# timer.net
KiCad netlist of a schematic drawn in EAGLE
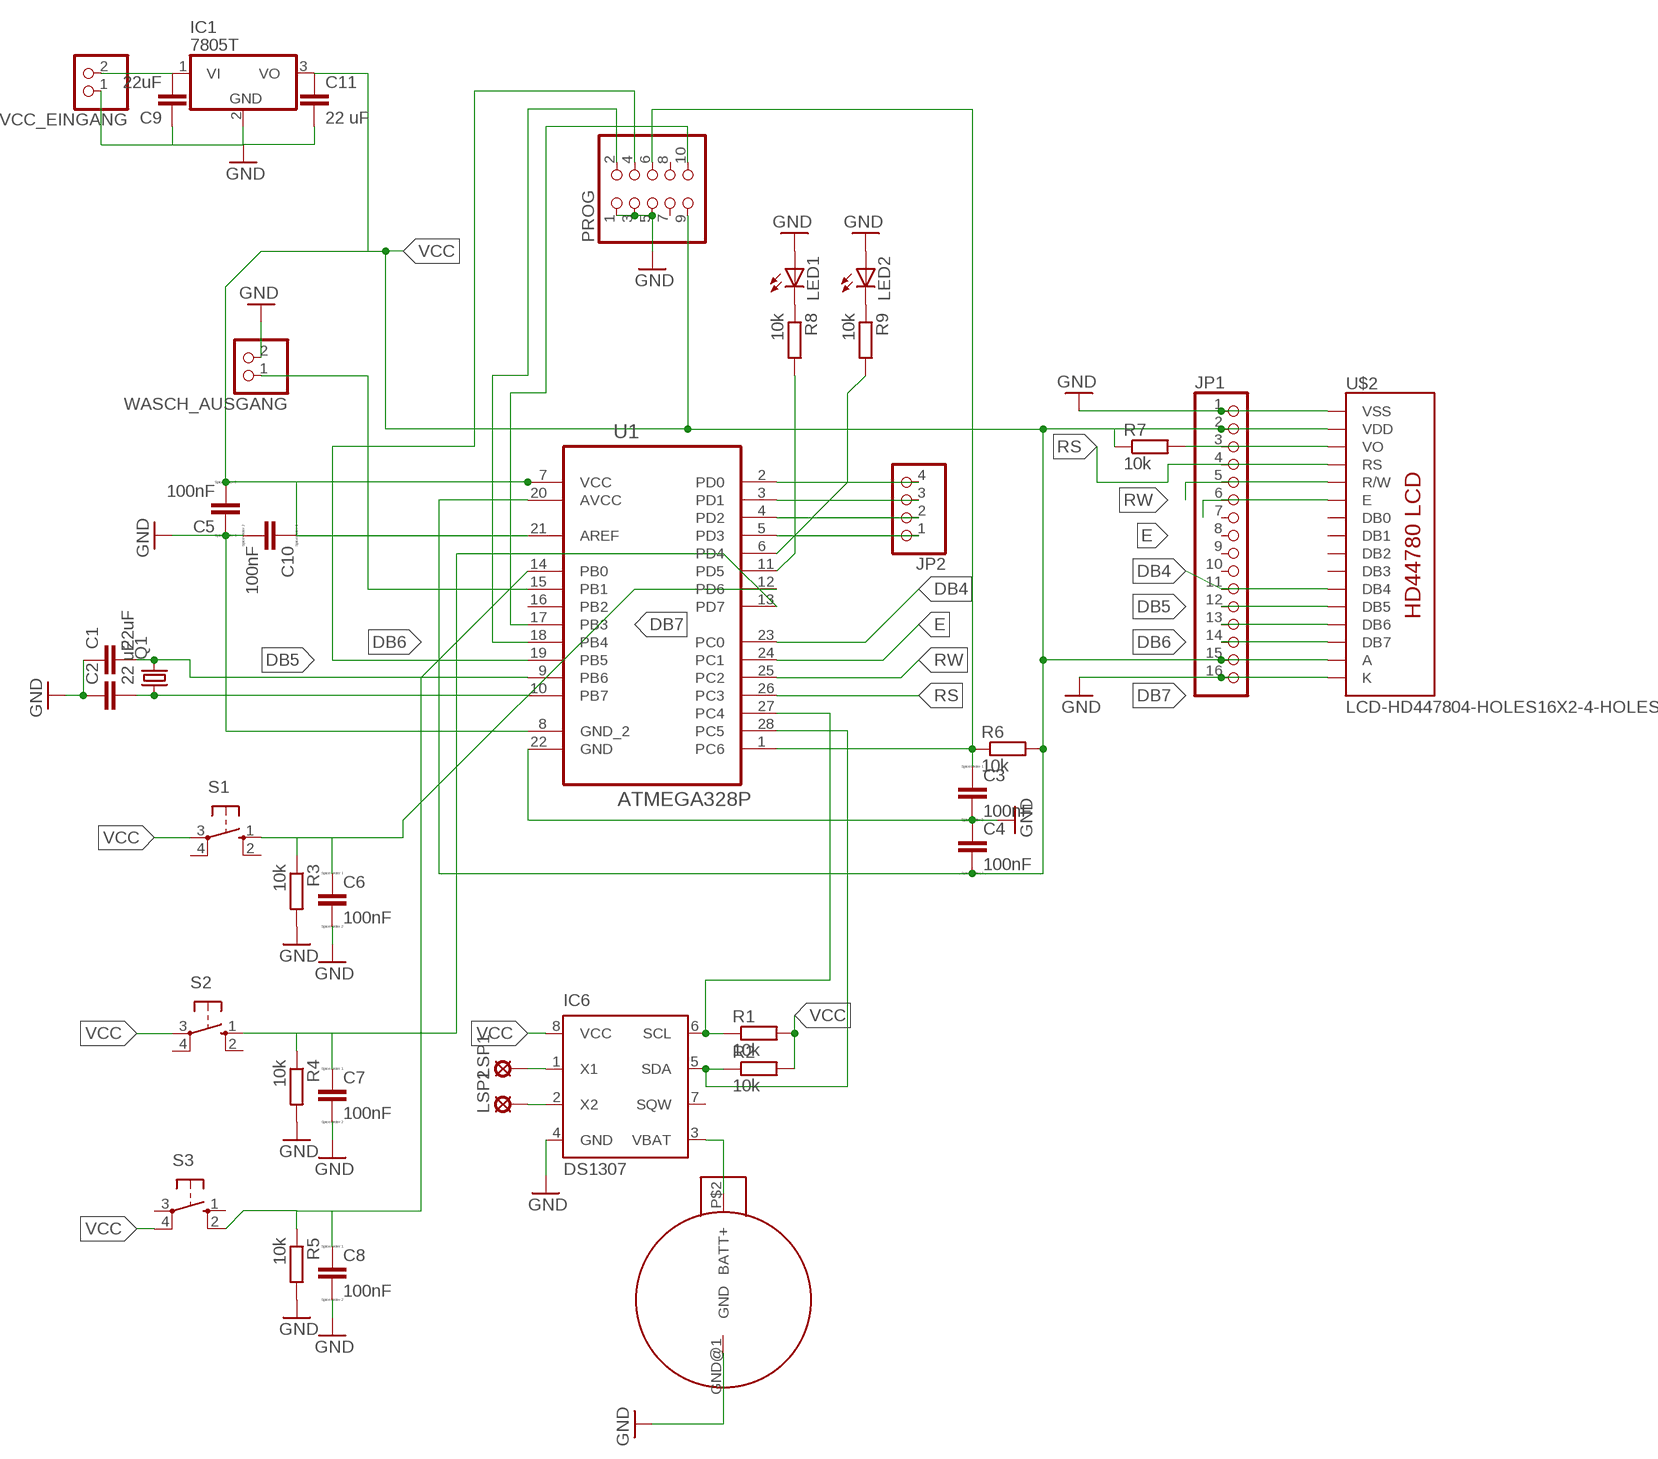
[diagram p0: schematic, sheet 1]

(export (version "E")
  (design (tool "Eeschema 10.0.6"))
  (components
    (comp (ref "C1")
      (value "22uF")
      (footprint "eagle-import:C025-025X050")
      (libsource (lib "eagle-import") (part "C-EU025-025X050"))
    )
    (comp (ref "C2")
      (value "22 uF")
      (footprint "eagle-import:C025-025X050")
      (libsource (lib "eagle-import") (part "C-EU025-025X050"))
    )
    (comp (ref "C3")
      (value "100nF")
      (footprint "eagle-import:C0603")
      (libsource (lib "eagle-import") (part "CC0603"))
    )
    (comp (ref "C4")
      (value "100nF")
      (footprint "eagle-import:C0603")
      (libsource (lib "eagle-import") (part "CC0603"))
    )
    (comp (ref "C5")
      (value "100nF")
      (footprint "eagle-import:C0603")
      (libsource (lib "eagle-import") (part "CC0603"))
    )
    (comp (ref "C6")
      (value "100nF")
      (footprint "eagle-import:C0603")
      (libsource (lib "eagle-import") (part "CC0603"))
    )
    (comp (ref "C7")
      (value "100nF")
      (footprint "eagle-import:C0603")
      (libsource (lib "eagle-import") (part "CC0603"))
    )
    (comp (ref "C8")
      (value "100nF")
      (footprint "eagle-import:C0603")
      (libsource (lib "eagle-import") (part "CC0603"))
    )
    (comp (ref "C9")
      (value "22uF")
      (footprint "eagle-import:C025-025X050")
      (libsource (lib "eagle-import") (part "C-EU025-025X050"))
    )
    (comp (ref "C10")
      (value "100nF")
      (footprint "eagle-import:C0603")
      (libsource (lib "eagle-import") (part "CC0603"))
    )
    (comp (ref "C11")
      (value "22 uF")
      (footprint "eagle-import:C025-025X050")
      (libsource (lib "eagle-import") (part "C-EU025-025X050"))
    )
    (comp (ref "IC1")
      (value "7805T")
      (footprint "eagle-import:TO220H")
      (libsource (lib "eagle-import") (part "78T05"))
    )
    (comp (ref "IC6")
      (value "DS1307")
      (footprint "eagle-import:DIL08")
      (libsource (lib "eagle-import") (part "DS1307"))
    )
    (comp (ref "JP1")
      (value "PINHD-1X16")
      (footprint "eagle-import:1X16")
      (libsource (lib "eagle-import") (part "PINHD-1X16"))
    )
    (comp (ref "JP2")
      (value "PINHD-1X4/90")
      (footprint "eagle-import:1X04_90")
      (libsource (lib "eagle-import") (part "PINHD-1X4/90"))
    )
    (comp (ref "LED1")
      (value "LED5MM")
      (footprint "eagle-import:LED5MM")
      (libsource (lib "eagle-import") (part "LED5MM"))
    )
    (comp (ref "LED2")
      (value "LED5MM")
      (footprint "eagle-import:LED5MM")
      (libsource (lib "eagle-import") (part "LED5MM"))
    )
    (comp (ref "LSP1")
      (value "LSP10")
      (footprint "eagle-import:LSP10")
      (libsource (lib "eagle-import") (part "LSP10"))
    )
    (comp (ref "LSP2")
      (value "LSP10")
      (footprint "eagle-import:LSP10")
      (libsource (lib "eagle-import") (part "LSP10"))
    )
    (comp (ref "PROG")
      (value "PINHD-2X5")
      (footprint "eagle-import:2X05")
      (libsource (lib "eagle-import") (part "PINHD-2X5"))
    )
    (comp (ref "Q1")
      (value "CRYSTALHC49U-V")
      (footprint "eagle-import:HC49U-V")
      (libsource (lib "eagle-import") (part "CRYSTALHC49U-V"))
    )
    (comp (ref "R1")
      (value "10k")
      (footprint "eagle-import:0204_7")
      (libsource (lib "eagle-import") (part "R-EU_0204/7"))
    )
    (comp (ref "R2")
      (value "10k")
      (footprint "eagle-import:0204_7")
      (libsource (lib "eagle-import") (part "R-EU_0204/7"))
    )
    (comp (ref "R3")
      (value "10k")
      (footprint "eagle-import:0204_7")
      (libsource (lib "eagle-import") (part "R-EU_0204/7"))
    )
    (comp (ref "R4")
      (value "10k")
      (footprint "eagle-import:0204_7")
      (libsource (lib "eagle-import") (part "R-EU_0204/7"))
    )
    (comp (ref "R5")
      (value "10k")
      (footprint "eagle-import:0204_7")
      (libsource (lib "eagle-import") (part "R-EU_0204/7"))
    )
    (comp (ref "R6")
      (value "10k")
      (footprint "eagle-import:0204_7")
      (libsource (lib "eagle-import") (part "R-EU_0204/7"))
    )
    (comp (ref "R7")
      (value "10k")
      (footprint "eagle-import:0204_7")
      (libsource (lib "eagle-import") (part "R-EU_0204/7"))
    )
    (comp (ref "R8")
      (value "10k")
      (footprint "eagle-import:0204_7")
      (libsource (lib "eagle-import") (part "R-EU_0204/7"))
    )
    (comp (ref "R9")
      (value "10k")
      (footprint "eagle-import:0204_7")
      (libsource (lib "eagle-import") (part "R-EU_0204/7"))
    )
    (comp (ref "S1")
      (value "10-XX")
      (footprint "eagle-import:B3F-10XX")
      (fields (field (name "MPN") "B3F-1000"))
      (libsource (lib "eagle-import") (part "10-XX"))
    )
    (comp (ref "S2")
      (value "10-XX")
      (footprint "eagle-import:B3F-10XX")
      (fields (field (name "MPN") "B3F-1000"))
      (libsource (lib "eagle-import") (part "10-XX"))
    )
    (comp (ref "S3")
      (value "10-XX")
      (footprint "eagle-import:B3F-10XX")
      (fields (field (name "MPN") "B3F-1000"))
      (libsource (lib "eagle-import") (part "10-XX"))
    )
    (comp (ref "U$1")
      (value "CR2032")
      (footprint "eagle-import:CR2023")
      (libsource (lib "eagle-import") (part "CR2032"))
    )
    (comp (ref "U$2")
      (value "LCD-HD447804-HOLES16X2-4-HOLES")
      (footprint "eagle-import:LCD-16X2-4HOLES")
      (libsource (lib "eagle-import") (part "LCD-HD4478016X2-4-HOLES4-HOLES"))
    )
    (comp (ref "U1")
      (value "ATMEGA328P")
      (footprint "eagle-import:DIP254P762X457-28")
      (fields (field (name "MPN") "ATMEGA328P-PU"))
      (libsource (lib "eagle-import") (part "ATMEGA328P-PU"))
    )
    (comp (ref "VCC_EINGANG")
      (value "PINHD-1X2")
      (footprint "eagle-import:1X02")
      (libsource (lib "eagle-import") (part "PINHD-1X2"))
    )
    (comp (ref "WASCH_AUSGANG")
      (value "PINHD-1X2")
      (footprint "eagle-import:1X02")
      (libsource (lib "eagle-import") (part "PINHD-1X2"))
    )
  )
  (nets
    (net (code "1") (name "DB4") (class "Default")
      (node (ref "JP1") (pin "11") (pinfunction "11_11") (pintype "passive"))
      (node (ref "U$2") (pin "11") (pinfunction "DB4_11") (pintype "bidirectional"))
      (node (ref "U1") (pin "23") (pinfunction "PC0_23") (pintype "bidirectional"))
    )
    (net (code "2") (name "DB5") (class "Default")
      (node (ref "JP1") (pin "12") (pinfunction "12_12") (pintype "passive"))
      (node (ref "PROG") (pin "4") (pinfunction "4_4") (pintype "passive"))
      (node (ref "U$2") (pin "12") (pinfunction "DB5_12") (pintype "bidirectional"))
      (node (ref "U1") (pin "19") (pinfunction "PB5_19") (pintype "bidirectional"))
    )
    (net (code "3") (name "DB6") (class "Default")
      (node (ref "JP1") (pin "13") (pinfunction "13_13") (pintype "passive"))
      (node (ref "PROG") (pin "2") (pinfunction "2_2") (pintype "passive"))
      (node (ref "U$2") (pin "13") (pinfunction "DB6_13") (pintype "bidirectional"))
      (node (ref "U1") (pin "18") (pinfunction "PB4_18") (pintype "bidirectional"))
    )
    (net (code "4") (name "DB7") (class "Default")
      (node (ref "JP1") (pin "14") (pinfunction "14_14") (pintype "passive"))
      (node (ref "PROG") (pin "10") (pinfunction "10_10") (pintype "passive"))
      (node (ref "U$2") (pin "14") (pinfunction "DB7_14") (pintype "bidirectional"))
      (node (ref "U1") (pin "17") (pinfunction "PB3_17") (pintype "bidirectional"))
    )
    (net (code "5") (name "E") (class "Default")
      (node (ref "JP1") (pin "6") (pinfunction "6_6") (pintype "passive"))
      (node (ref "U$2") (pin "6") (pinfunction "E_6") (pintype "input"))
      (node (ref "U1") (pin "24") (pinfunction "PC1_24") (pintype "bidirectional"))
    )
    (net (code "6") (name "GND") (class "Default")
      (node (ref "C1") (pin "1") (pinfunction "1_1") (pintype "passive"))
      (node (ref "C10") (pin "2") (pinfunction "2_2") (pintype "passive"))
      (node (ref "C11") (pin "2") (pinfunction "2_2") (pintype "passive"))
      (node (ref "C2") (pin "1") (pinfunction "1_1") (pintype "passive"))
      (node (ref "C3") (pin "2") (pinfunction "2_2") (pintype "passive"))
      (node (ref "C4") (pin "1") (pinfunction "1_1") (pintype "passive"))
      (node (ref "C5") (pin "1") (pinfunction "1_1") (pintype "passive"))
      (node (ref "C6") (pin "2") (pinfunction "2_2") (pintype "passive"))
      (node (ref "C7") (pin "2") (pinfunction "2_2") (pintype "passive"))
      (node (ref "C8") (pin "2") (pinfunction "2_2") (pintype "passive"))
      (node (ref "C9") (pin "1") (pinfunction "1_1") (pintype "passive"))
      (node (ref "IC1") (pin "2") (pinfunction "GND_2") (pintype "passive"))
      (node (ref "IC6") (pin "4") (pinfunction "GND_4") (pintype "power_in"))
      (node (ref "JP1") (pin "1") (pinfunction "1_1") (pintype "passive"))
      (node (ref "JP1") (pin "16") (pinfunction "16_16") (pintype "passive"))
      (node (ref "LED1") (pin "A") (pinfunction "A_A") (pintype "passive"))
      (node (ref "LED2") (pin "A") (pinfunction "A_A") (pintype "passive"))
      (node (ref "PROG") (pin "1") (pinfunction "1_1") (pintype "passive"))
      (node (ref "PROG") (pin "3") (pinfunction "3_3") (pintype "passive"))
      (node (ref "PROG") (pin "5") (pinfunction "5_5") (pintype "passive"))
      (node (ref "R3") (pin "2") (pinfunction "2_2") (pintype "passive"))
      (node (ref "R4") (pin "2") (pinfunction "2_2") (pintype "passive"))
      (node (ref "R5") (pin "2") (pinfunction "2_2") (pintype "passive"))
      (node (ref "U$1") (pin "GND@1") (pinfunction "GND_GND@1") (pintype "power_in"))
      (node (ref "U$2") (pin "1") (pinfunction "VSS_1") (pintype "power_in"))
      (node (ref "U$2") (pin "16") (pinfunction "K_16") (pintype "power_in"))
      (node (ref "U1") (pin "22") (pinfunction "GND_22") (pintype "passive"))
      (node (ref "U1") (pin "8") (pinfunction "GND_2_8") (pintype "passive"))
      (node (ref "VCC_EINGANG") (pin "1") (pinfunction "1_1") (pintype "passive"))
      (node (ref "WASCH_AUSGANG") (pin "2") (pinfunction "2_2") (pintype "passive"))
    )
    (net (code "7") (name "Net-(IC1-VI)") (class "Default")
      (node (ref "C9") (pin "2") (pinfunction "2_2") (pintype "passive"))
      (node (ref "IC1") (pin "1") (pinfunction "VI_1") (pintype "input"))
      (node (ref "VCC_EINGANG") (pin "2") (pinfunction "2_2") (pintype "passive"))
    )
    (net (code "8") (name "Net-(IC6-SCL)") (class "Default")
      (node (ref "IC6") (pin "6") (pinfunction "SCL_6") (pintype "input"))
      (node (ref "R1") (pin "1") (pinfunction "1_1") (pintype "passive"))
      (node (ref "U1") (pin "27") (pinfunction "PC4_27") (pintype "bidirectional"))
    )
    (net (code "9") (name "Net-(IC6-SDA)") (class "Default")
      (node (ref "IC6") (pin "5") (pinfunction "SDA_5") (pintype "bidirectional"))
      (node (ref "R2") (pin "1") (pinfunction "1_1") (pintype "passive"))
      (node (ref "U1") (pin "28") (pinfunction "PC5_28") (pintype "bidirectional"))
    )
    (net (code "10") (name "Net-(IC6-VBAT)") (class "Default")
      (node (ref "IC6") (pin "3") (pinfunction "VBAT_3") (pintype "passive"))
      (node (ref "U$1") (pin "P$2") (pinfunction "BATT+_P$2") (pintype "output"))
    )
    (net (code "11") (name "Net-(IC6-X1)") (class "Default")
      (node (ref "IC6") (pin "1") (pinfunction "X1_1") (pintype "input"))
      (node (ref "LSP1") (pin "MP") (pinfunction "MP_MP") (pintype "passive"))
    )
    (net (code "12") (name "Net-(IC6-X2)") (class "Default")
      (node (ref "IC6") (pin "2") (pinfunction "X2_2") (pintype "output"))
      (node (ref "LSP2") (pin "MP") (pinfunction "MP_MP") (pintype "passive"))
    )
    (net (code "13") (name "Net-(LED1-C)") (class "Default")
      (node (ref "LED1") (pin "K") (pinfunction "C_K") (pintype "passive"))
      (node (ref "R8") (pin "1") (pinfunction "1_1") (pintype "passive"))
    )
    (net (code "14") (name "Net-(LED2-C)") (class "Default")
      (node (ref "LED2") (pin "K") (pinfunction "C_K") (pintype "passive"))
      (node (ref "R9") (pin "1") (pinfunction "1_1") (pintype "passive"))
    )
    (net (code "15") (name "Net-(S1-S)") (class "Default")
      (node (ref "C6") (pin "1") (pinfunction "1_1") (pintype "passive"))
      (node (ref "R3") (pin "1") (pinfunction "1_1") (pintype "passive"))
      (node (ref "S1") (pin "1") (pinfunction "S_1") (pintype "passive"))
      (node (ref "U1") (pin "12") (pinfunction "PD6_12") (pintype "bidirectional"))
    )
    (net (code "16") (name "Net-(S2-S)") (class "Default")
      (node (ref "C7") (pin "1") (pinfunction "1_1") (pintype "passive"))
      (node (ref "R4") (pin "1") (pinfunction "1_1") (pintype "passive"))
      (node (ref "S2") (pin "1") (pinfunction "S_1") (pintype "passive"))
      (node (ref "U1") (pin "13") (pinfunction "PD7_13") (pintype "bidirectional"))
    )
    (net (code "17") (name "Net-(S3-S1)") (class "Default")
      (node (ref "C8") (pin "1") (pinfunction "1_1") (pintype "passive"))
      (node (ref "R5") (pin "1") (pinfunction "1_1") (pintype "passive"))
      (node (ref "S3") (pin "2") (pinfunction "S1_2") (pintype "passive"))
      (node (ref "U1") (pin "14") (pinfunction "PB0_14") (pintype "bidirectional"))
    )
    (net (code "18") (name "Net-(U$2-VO)") (class "Default")
      (node (ref "JP1") (pin "3") (pinfunction "3_3") (pintype "passive"))
      (node (ref "R7") (pin "2") (pinfunction "2_2") (pintype "passive"))
      (node (ref "U$2") (pin "3") (pinfunction "VO_3") (pintype "bidirectional"))
    )
    (net (code "19") (name "Net-(U1-PB1)") (class "Default")
      (node (ref "U1") (pin "15") (pinfunction "PB1_15") (pintype "bidirectional"))
      (node (ref "WASCH_AUSGANG") (pin "1") (pinfunction "1_1") (pintype "passive"))
    )
    (net (code "20") (name "Net-(U1-PB6)") (class "Default")
      (node (ref "C1") (pin "2") (pinfunction "2_2") (pintype "passive"))
      (node (ref "Q1") (pin "2") (pinfunction "2_2") (pintype "passive"))
      (node (ref "U1") (pin "9") (pinfunction "PB6_9") (pintype "bidirectional"))
    )
    (net (code "21") (name "Net-(U1-PB7)") (class "Default")
      (node (ref "C2") (pin "2") (pinfunction "2_2") (pintype "passive"))
      (node (ref "Q1") (pin "1") (pinfunction "1_1") (pintype "passive"))
      (node (ref "U1") (pin "10") (pinfunction "PB7_10") (pintype "bidirectional"))
    )
    (net (code "22") (name "Net-(U1-PC6)") (class "Default")
      (node (ref "C3") (pin "1") (pinfunction "1_1") (pintype "passive"))
      (node (ref "PROG") (pin "6") (pinfunction "6_6") (pintype "passive"))
      (node (ref "R6") (pin "1") (pinfunction "1_1") (pintype "passive"))
      (node (ref "U1") (pin "1") (pinfunction "PC6_1") (pintype "bidirectional"))
    )
    (net (code "23") (name "Net-(U1-PD0)") (class "Default")
      (node (ref "JP2") (pin "4") (pinfunction "4_4") (pintype "passive"))
      (node (ref "U1") (pin "2") (pinfunction "PD0_2") (pintype "bidirectional"))
    )
    (net (code "24") (name "Net-(U1-PD1)") (class "Default")
      (node (ref "JP2") (pin "3") (pinfunction "3_3") (pintype "passive"))
      (node (ref "U1") (pin "3") (pinfunction "PD1_3") (pintype "bidirectional"))
    )
    (net (code "25") (name "Net-(U1-PD2)") (class "Default")
      (node (ref "JP2") (pin "2") (pinfunction "2_2") (pintype "passive"))
      (node (ref "U1") (pin "4") (pinfunction "PD2_4") (pintype "bidirectional"))
    )
    (net (code "26") (name "Net-(U1-PD3)") (class "Default")
      (node (ref "JP2") (pin "1") (pinfunction "1_1") (pintype "passive"))
      (node (ref "U1") (pin "5") (pinfunction "PD3_5") (pintype "bidirectional"))
    )
    (net (code "27") (name "Net-(U1-PD4)") (class "Default")
      (node (ref "R9") (pin "2") (pinfunction "2_2") (pintype "passive"))
      (node (ref "U1") (pin "6") (pinfunction "PD4_6") (pintype "bidirectional"))
    )
    (net (code "28") (name "Net-(U1-PD5)") (class "Default")
      (node (ref "R8") (pin "2") (pinfunction "2_2") (pintype "passive"))
      (node (ref "U1") (pin "11") (pinfunction "PD5_11") (pintype "bidirectional"))
    )
    (net (code "29") (name "RS") (class "Default")
      (node (ref "JP1") (pin "4") (pinfunction "4_4") (pintype "passive"))
      (node (ref "U$2") (pin "4") (pinfunction "RS_4") (pintype "input"))
      (node (ref "U1") (pin "26") (pinfunction "PC3_26") (pintype "bidirectional"))
    )
    (net (code "30") (name "RW") (class "Default")
      (node (ref "JP1") (pin "5") (pinfunction "5_5") (pintype "passive"))
      (node (ref "U$2") (pin "5") (pinfunction "R/W_5") (pintype "input"))
      (node (ref "U1") (pin "25") (pinfunction "PC2_25") (pintype "bidirectional"))
    )
    (net (code "31") (name "VCC") (class "Default")
      (node (ref "C10") (pin "1") (pinfunction "1_1") (pintype "passive"))
      (node (ref "C11") (pin "1") (pinfunction "1_1") (pintype "passive"))
      (node (ref "C4") (pin "2") (pinfunction "2_2") (pintype "passive"))
      (node (ref "C5") (pin "2") (pinfunction "2_2") (pintype "passive"))
      (node (ref "IC1") (pin "3") (pinfunction "VO_3") (pintype "passive"))
      (node (ref "IC6") (pin "8") (pinfunction "VCC_8") (pintype "power_in"))
      (node (ref "JP1") (pin "15") (pinfunction "15_15") (pintype "passive"))
      (node (ref "JP1") (pin "2") (pinfunction "2_2") (pintype "passive"))
      (node (ref "PROG") (pin "9") (pinfunction "9_9") (pintype "passive"))
      (node (ref "R1") (pin "2") (pinfunction "2_2") (pintype "passive"))
      (node (ref "R2") (pin "2") (pinfunction "2_2") (pintype "passive"))
      (node (ref "R6") (pin "2") (pinfunction "2_2") (pintype "passive"))
      (node (ref "R7") (pin "1") (pinfunction "1_1") (pintype "passive"))
      (node (ref "S1") (pin "3") (pinfunction "P_3") (pintype "passive"))
      (node (ref "S2") (pin "3") (pinfunction "P_3") (pintype "passive"))
      (node (ref "S3") (pin "4") (pinfunction "P1_4") (pintype "passive"))
      (node (ref "U$2") (pin "15") (pinfunction "A_15") (pintype "power_in"))
      (node (ref "U$2") (pin "2") (pinfunction "VDD_2") (pintype "power_in"))
      (node (ref "U1") (pin "20") (pinfunction "AVCC_20") (pintype "power_in"))
      (node (ref "U1") (pin "21") (pinfunction "AREF_21") (pintype "input"))
      (node (ref "U1") (pin "7") (pinfunction "VCC_7") (pintype "power_in"))
    )
    (net (code "32") (name "unconnected-(IC6-SQW-Pad7)") (class "Default")
      (node (ref "IC6") (pin "7") (pinfunction "SQW_7") (pintype "open_collector"))
    )
    (net (code "33") (name "unconnected-(JP1-Pad7)") (class "Default")
      (node (ref "JP1") (pin "7") (pinfunction "7_7") (pintype "passive"))
    )
    (net (code "34") (name "unconnected-(JP1-Pad8)") (class "Default")
      (node (ref "JP1") (pin "8") (pinfunction "8_8") (pintype "passive"))
    )
    (net (code "35") (name "unconnected-(JP1-Pad9)") (class "Default")
      (node (ref "JP1") (pin "9") (pinfunction "9_9") (pintype "passive"))
    )
    (net (code "36") (name "unconnected-(JP1-Pad10)") (class "Default")
      (node (ref "JP1") (pin "10") (pinfunction "10_10") (pintype "passive"))
    )
    (net (code "37") (name "unconnected-(PROG-Pad7)") (class "Default")
      (node (ref "PROG") (pin "7") (pinfunction "7_7") (pintype "passive"))
    )
    (net (code "38") (name "unconnected-(PROG-Pad8)") (class "Default")
      (node (ref "PROG") (pin "8") (pinfunction "8_8") (pintype "passive"))
    )
    (net (code "39") (name "unconnected-(S1-P1-Pad4)") (class "Default")
      (node (ref "S1") (pin "4") (pinfunction "P1_4") (pintype "passive"))
    )
    (net (code "40") (name "unconnected-(S1-S1-Pad2)") (class "Default")
      (node (ref "S1") (pin "2") (pinfunction "S1_2") (pintype "passive"))
    )
    (net (code "41") (name "unconnected-(S2-P1-Pad4)") (class "Default")
      (node (ref "S2") (pin "4") (pinfunction "P1_4") (pintype "passive"))
    )
    (net (code "42") (name "unconnected-(S2-S1-Pad2)") (class "Default")
      (node (ref "S2") (pin "2") (pinfunction "S1_2") (pintype "passive"))
    )
    (net (code "43") (name "unconnected-(S3-P-Pad3)") (class "Default")
      (node (ref "S3") (pin "3") (pinfunction "P_3") (pintype "passive"))
    )
    (net (code "44") (name "unconnected-(S3-S-Pad1)") (class "Default")
      (node (ref "S3") (pin "1") (pinfunction "S_1") (pintype "passive"))
    )
    (net (code "45") (name "unconnected-(U$2-DB0-Pad7)") (class "Default")
      (node (ref "U$2") (pin "7") (pinfunction "DB0_7") (pintype "bidirectional"))
    )
    (net (code "46") (name "unconnected-(U$2-DB1-Pad8)") (class "Default")
      (node (ref "U$2") (pin "8") (pinfunction "DB1_8") (pintype "bidirectional"))
    )
    (net (code "47") (name "unconnected-(U$2-DB2-Pad9)") (class "Default")
      (node (ref "U$2") (pin "9") (pinfunction "DB2_9") (pintype "bidirectional"))
    )
    (net (code "48") (name "unconnected-(U$2-DB3-Pad10)") (class "Default")
      (node (ref "U$2") (pin "10") (pinfunction "DB3_10") (pintype "bidirectional"))
    )
    (net (code "49") (name "unconnected-(U1-PB2-Pad16)") (class "Default")
      (node (ref "U1") (pin "16") (pinfunction "PB2_16") (pintype "bidirectional"))
    )
  )
)
